# Mechanical.net
KiCad netlist of a schematic drawn in Altium Designer
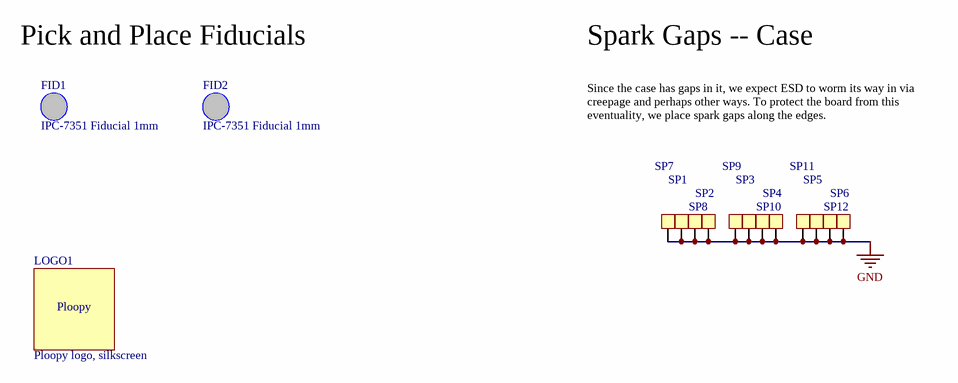
[diagram p0: Mechanical.SchDoc]

(export (version "E")
  (design (tool "Eeschema 10.0.6"))
  (components
    (comp (ref "FID1")
      (value "IPC-7351 Fiducial 1mm")
      (footprint "FIDUCIAL_1.5")
      (libsource (lib "Mechanical") (part "FIDUCIAL_1.5"))
    )
    (comp (ref "FID2")
      (value "IPC-7351 Fiducial 1mm")
      (footprint "FIDUCIAL_1.5")
      (libsource (lib "Mechanical") (part "FIDUCIAL_1.5"))
    )
    (comp (ref "LOGO1")
      (value "Ploopy logo, silkscreen")
      (footprint "PloopyLogo")
      (libsource (lib "Graphics") (part "PloopyLogo"))
    )
    (comp (ref "SP1")
      (value "Spark Gap")
      (footprint "SparkGap")
      (description "Open square pad for spark gapping")
      (libsource (lib "PCBFeatures") (part "Spark Gap"))
    )
    (comp (ref "SP2")
      (value "Spark Gap")
      (footprint "SparkGap")
      (description "Open square pad for spark gapping")
      (libsource (lib "PCBFeatures") (part "Spark Gap"))
    )
    (comp (ref "SP3")
      (value "Spark Gap")
      (footprint "SparkGap")
      (description "Open square pad for spark gapping")
      (libsource (lib "PCBFeatures") (part "Spark Gap"))
    )
    (comp (ref "SP4")
      (value "Spark Gap")
      (footprint "SparkGap")
      (description "Open square pad for spark gapping")
      (libsource (lib "PCBFeatures") (part "Spark Gap"))
    )
    (comp (ref "SP5")
      (value "Spark Gap")
      (footprint "SparkGap")
      (description "Open square pad for spark gapping")
      (libsource (lib "PCBFeatures") (part "Spark Gap"))
    )
    (comp (ref "SP6")
      (value "Spark Gap")
      (footprint "SparkGap")
      (description "Open square pad for spark gapping")
      (libsource (lib "PCBFeatures") (part "Spark Gap"))
    )
    (comp (ref "SP7")
      (value "Spark Gap")
      (footprint "SparkGap")
      (description "Open square pad for spark gapping")
      (libsource (lib "PCBFeatures") (part "Spark Gap"))
    )
    (comp (ref "SP8")
      (value "Spark Gap")
      (footprint "SparkGap")
      (description "Open square pad for spark gapping")
      (libsource (lib "PCBFeatures") (part "Spark Gap"))
    )
    (comp (ref "SP9")
      (value "Spark Gap")
      (footprint "SparkGap")
      (description "Open square pad for spark gapping")
      (libsource (lib "PCBFeatures") (part "Spark Gap"))
    )
    (comp (ref "SP10")
      (value "Spark Gap")
      (footprint "SparkGap")
      (description "Open square pad for spark gapping")
      (libsource (lib "PCBFeatures") (part "Spark Gap"))
    )
    (comp (ref "SP11")
      (value "Spark Gap")
      (footprint "SparkGap")
      (description "Open square pad for spark gapping")
      (libsource (lib "PCBFeatures") (part "Spark Gap"))
    )
    (comp (ref "SP12")
      (value "Spark Gap")
      (footprint "SparkGap")
      (description "Open square pad for spark gapping")
      (libsource (lib "PCBFeatures") (part "Spark Gap"))
    )
  )
  (nets
    (net (code "1") (name "GND") (class "Default")
      (node (ref "SP1") (pin "1") (pinfunction "1_1") (pintype "passive"))
      (node (ref "SP10") (pin "1") (pinfunction "1_1") (pintype "passive"))
      (node (ref "SP11") (pin "1") (pinfunction "1_1") (pintype "passive"))
      (node (ref "SP12") (pin "1") (pinfunction "1_1") (pintype "passive"))
      (node (ref "SP2") (pin "1") (pinfunction "1_1") (pintype "passive"))
      (node (ref "SP3") (pin "1") (pinfunction "1_1") (pintype "passive"))
      (node (ref "SP4") (pin "1") (pinfunction "1_1") (pintype "passive"))
      (node (ref "SP5") (pin "1") (pinfunction "1_1") (pintype "passive"))
      (node (ref "SP6") (pin "1") (pinfunction "1_1") (pintype "passive"))
      (node (ref "SP7") (pin "1") (pinfunction "1_1") (pintype "passive"))
      (node (ref "SP8") (pin "1") (pinfunction "1_1") (pintype "passive"))
      (node (ref "SP9") (pin "1") (pinfunction "1_1") (pintype "passive"))
    )
    (net (code "2") (name "unconnected-(FID1-Pad1)") (class "Default")
      (node (ref "FID1") (pin "1") (pinfunction "1_1") (pintype "passive"))
    )
    (net (code "3") (name "unconnected-(FID2-Pad1)") (class "Default")
      (node (ref "FID2") (pin "1") (pinfunction "1_1") (pintype "passive"))
    )
  )
)
